# 01-PCIe.net
KiCad netlist of a schematic drawn in Altium Designer
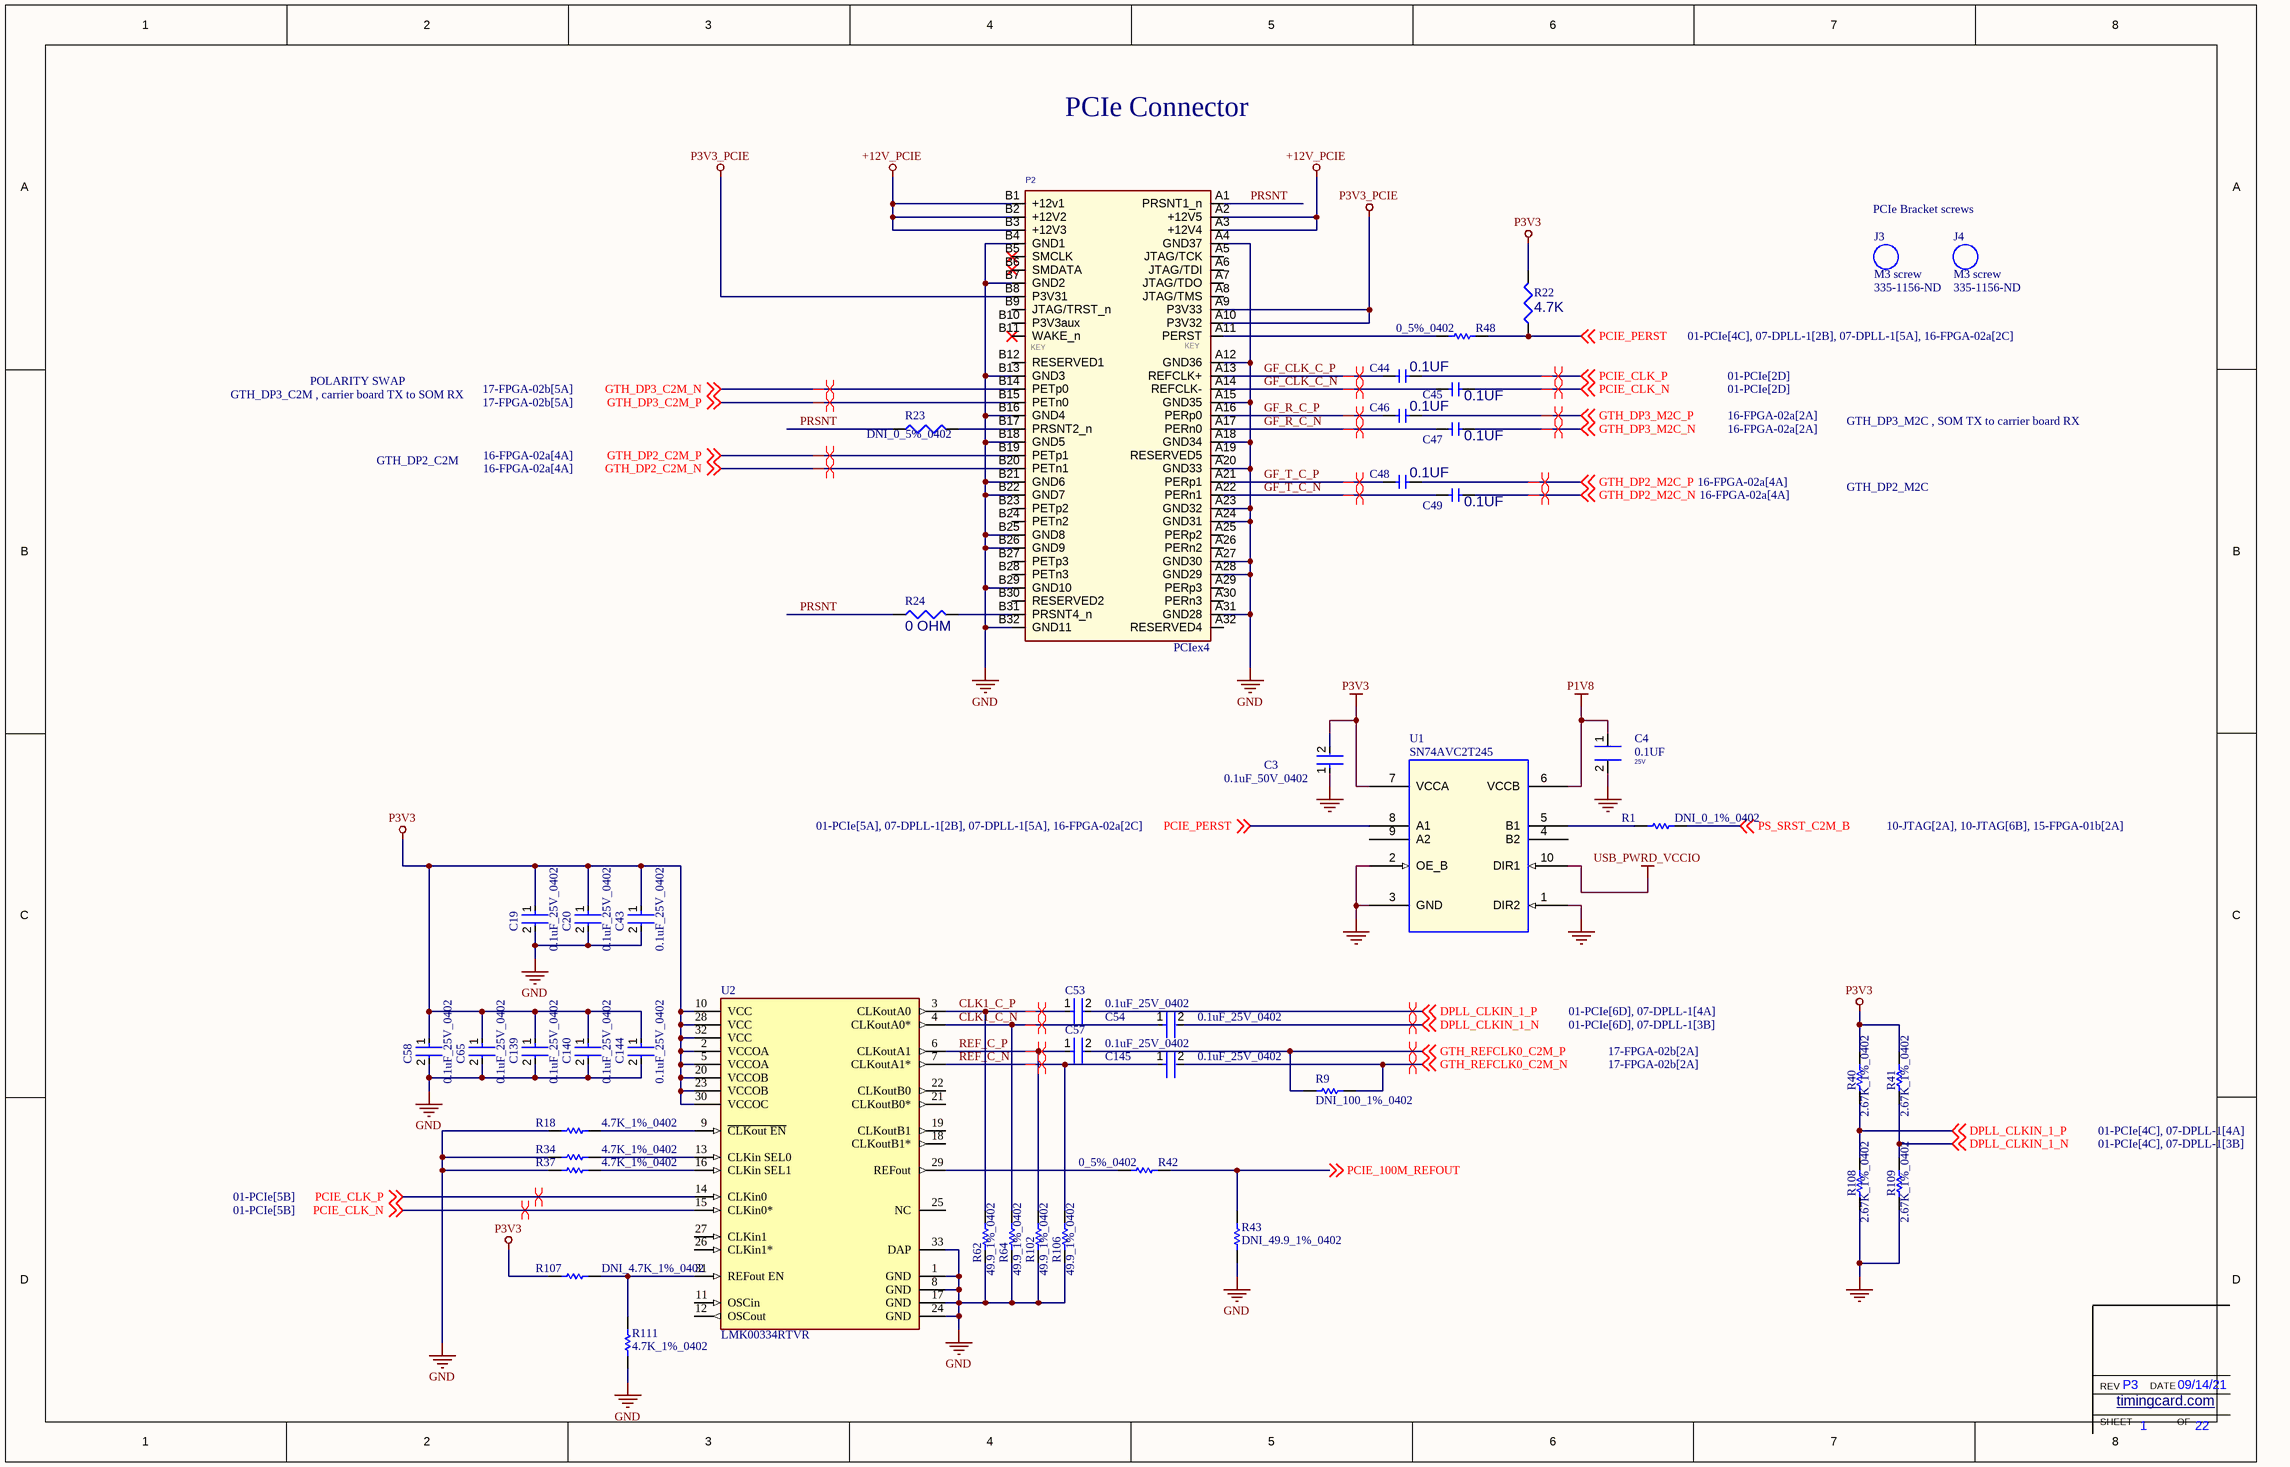
[diagram p0: 01-PCIe.SchDoc]

(export (version "E")
  (design (tool "Eeschema 10.0.6"))
  (components
    (comp (ref "C3")
      (value "0.1uF_50V_0402")
      (footprint "FP-C1005-050-0_05-IPC_C")
      (description "Multilayer Ceramic Capacitors 100nF ±10% 50V X7R SMD 0402")
      (fields (field (name "VOLTAGE") "50V") (field (name "TOLERANCE") "10%"))
      (libsource (lib "Altium Content Vault") (part "b4654b650e69147ec39a6b967a45e02"))
    )
    (comp (ref "C4")
      (value "0.1UF")
      (footprint "CAPC100X50X55")
      (description "Cap Cer 100nF 10% 25V X5R 0402")
      (fields
        (field (name "VOLTAGE") "25V")
        (field (name "MANUFACTURER") "TAIYO YUDEN")
        (field (name "AGILE PART NUMBER") "CAP-00068-01")
        (field (name "OWNER") "4001")
      )
      (libsource (lib "*") (part "CAP_NP"))
    )
    (comp (ref "C19")
      (value "0.1uF_25V_0402")
      (footprint "FP-0402-L_1_0_1-W_0_5_0_1-IPC_C")
      (description "General Purpose Ceramic Capacitor, 0402, 100nF, 10%, X7R, 15%, 25V")
      (fields (field (name "VOLTAGE") "25V") (field (name "TOLERANCE") "10%"))
      (libsource (lib "Altium Content Vault") (part "b4654b650e69147ec39a6b967a45e02"))
    )
    (comp (ref "C20")
      (value "0.1uF_25V_0402")
      (footprint "FP-0402-L_1_0_1-W_0_5_0_1-IPC_C")
      (description "General Purpose Ceramic Capacitor, 0402, 100nF, 10%, X7R, 15%, 25V")
      (fields (field (name "VOLTAGE") "25V") (field (name "TOLERANCE") "10%"))
      (libsource (lib "Altium Content Vault") (part "b4654b650e69147ec39a6b967a45e02"))
    )
    (comp (ref "C43")
      (value "0.1uF_25V_0402")
      (footprint "FP-0402-L_1_0_1-W_0_5_0_1-IPC_C")
      (description "General Purpose Ceramic Capacitor, 0402, 100nF, 10%, X7R, 15%, 25V")
      (fields (field (name "VOLTAGE") "25V") (field (name "TOLERANCE") "10%"))
      (libsource (lib "Altium Content Vault") (part "b4654b650e69147ec39a6b967a45e02"))
    )
    (comp (ref "C44")
      (value "0.1UF")
      (footprint "CAPC1005X06N")
      (description "CAP, CER, 0.1UF, 50V, 10%, X7R, AEC-Q200, 0402")
      (fields
        (field (name "MFG PART NUM") "CGA2B3X7R1H104K050BB")
        (field (name "VALENTIUM PART NUM") "<VALENTIUM>")
      )
      (libsource (lib "Capacitors") (part "CAP_0402_0.1UF_50V"))
    )
    (comp (ref "C45")
      (value "0.1UF")
      (footprint "CAPC1005X06N")
      (description "CAP, CER, 0.1UF, 50V, 10%, X7R, AEC-Q200, 0402")
      (fields
        (field (name "MFG PART NUM") "CGA2B3X7R1H104K050BB")
        (field (name "VALENTIUM PART NUM") "<VALENTIUM>")
      )
      (libsource (lib "Capacitors") (part "CAP_0402_0.1UF_50V"))
    )
    (comp (ref "C46")
      (value "0.1UF")
      (footprint "CAPC1005X06N")
      (description "CAP, CER, 0.1UF, 50V, 10%, X7R, AEC-Q200, 0402")
      (fields
        (field (name "MFG PART NUM") "CGA2B3X7R1H104K050BB")
        (field (name "VALENTIUM PART NUM") "<VALENTIUM>")
      )
      (libsource (lib "Capacitors") (part "CAP_0402_0.1UF_50V"))
    )
    (comp (ref "C47")
      (value "0.1UF")
      (footprint "CAPC1005X06N")
      (description "CAP, CER, 0.1UF, 50V, 10%, X7R, AEC-Q200, 0402")
      (fields
        (field (name "MFG PART NUM") "CGA2B3X7R1H104K050BB")
        (field (name "VALENTIUM PART NUM") "<VALENTIUM>")
      )
      (libsource (lib "Capacitors") (part "CAP_0402_0.1UF_50V"))
    )
    (comp (ref "C48")
      (value "0.1UF")
      (footprint "CAPC1005X06N")
      (description "CAP, CER, 0.1UF, 50V, 10%, X7R, AEC-Q200, 0402")
      (fields
        (field (name "MFG PART NUM") "CGA2B3X7R1H104K050BB")
        (field (name "VALENTIUM PART NUM") "<VALENTIUM>")
      )
      (libsource (lib "Capacitors") (part "CAP_0402_0.1UF_50V"))
    )
    (comp (ref "C49")
      (value "0.1UF")
      (footprint "CAPC1005X06N")
      (description "CAP, CER, 0.1UF, 50V, 10%, X7R, AEC-Q200, 0402")
      (fields
        (field (name "MFG PART NUM") "CGA2B3X7R1H104K050BB")
        (field (name "VALENTIUM PART NUM") "<VALENTIUM>")
      )
      (libsource (lib "Capacitors") (part "CAP_0402_0.1UF_50V"))
    )
    (comp (ref "C53")
      (value "0.1uF_25V_0402")
      (footprint "FP-0402-L_1_0_1-W_0_5_0_1-IPC_C")
      (description "General Purpose Ceramic Capacitor, 0402, 100nF, 10%, X7R, 15%, 25V")
      (fields (field (name "VOLTAGE") "25V") (field (name "TOLERANCE") "10%"))
      (libsource (lib "Altium Content Vault") (part "b4654b650e69147ec39a6b967a45e02"))
    )
    (comp (ref "C54")
      (value "0.1uF_25V_0402")
      (footprint "FP-0402-L_1_0_1-W_0_5_0_1-IPC_C")
      (description "General Purpose Ceramic Capacitor, 0402, 100nF, 10%, X7R, 15%, 25V")
      (fields (field (name "VOLTAGE") "25V") (field (name "TOLERANCE") "10%"))
      (libsource (lib "Altium Content Vault") (part "b4654b650e69147ec39a6b967a45e02"))
    )
    (comp (ref "C57")
      (value "0.1uF_25V_0402")
      (footprint "FP-0402-L_1_0_1-W_0_5_0_1-IPC_C")
      (description "General Purpose Ceramic Capacitor, 0402, 100nF, 10%, X7R, 15%, 25V")
      (fields (field (name "VOLTAGE") "25V") (field (name "TOLERANCE") "10%"))
      (libsource (lib "Altium Content Vault") (part "b4654b650e69147ec39a6b967a45e02"))
    )
    (comp (ref "C58")
      (value "0.1uF_25V_0402")
      (footprint "FP-0402-L_1_0_1-W_0_5_0_1-IPC_C")
      (description "General Purpose Ceramic Capacitor, 0402, 100nF, 10%, X7R, 15%, 25V")
      (fields (field (name "VOLTAGE") "25V") (field (name "TOLERANCE") "10%"))
      (libsource (lib "Altium Content Vault") (part "b4654b650e69147ec39a6b967a45e02"))
    )
    (comp (ref "C65")
      (value "0.1uF_25V_0402")
      (footprint "FP-0402-L_1_0_1-W_0_5_0_1-IPC_C")
      (description "General Purpose Ceramic Capacitor, 0402, 100nF, 10%, X7R, 15%, 25V")
      (fields (field (name "VOLTAGE") "25V") (field (name "TOLERANCE") "10%"))
      (libsource (lib "Altium Content Vault") (part "b4654b650e69147ec39a6b967a45e02"))
    )
    (comp (ref "C139")
      (value "0.1uF_25V_0402")
      (footprint "FP-0402-L_1_0_1-W_0_5_0_1-IPC_C")
      (description "General Purpose Ceramic Capacitor, 0402, 100nF, 10%, X7R, 15%, 25V")
      (fields (field (name "VOLTAGE") "25V") (field (name "TOLERANCE") "10%"))
      (libsource (lib "Altium Content Vault") (part "b4654b650e69147ec39a6b967a45e02"))
    )
    (comp (ref "C140")
      (value "0.1uF_25V_0402")
      (footprint "FP-0402-L_1_0_1-W_0_5_0_1-IPC_C")
      (description "General Purpose Ceramic Capacitor, 0402, 100nF, 10%, X7R, 15%, 25V")
      (fields (field (name "VOLTAGE") "25V") (field (name "TOLERANCE") "10%"))
      (libsource (lib "Altium Content Vault") (part "b4654b650e69147ec39a6b967a45e02"))
    )
    (comp (ref "C144")
      (value "0.1uF_25V_0402")
      (footprint "FP-0402-L_1_0_1-W_0_5_0_1-IPC_C")
      (description "General Purpose Ceramic Capacitor, 0402, 100nF, 10%, X7R, 15%, 25V")
      (fields (field (name "VOLTAGE") "25V") (field (name "TOLERANCE") "10%"))
      (libsource (lib "Altium Content Vault") (part "b4654b650e69147ec39a6b967a45e02"))
    )
    (comp (ref "C145")
      (value "0.1uF_25V_0402")
      (footprint "FP-0402-L_1_0_1-W_0_5_0_1-IPC_C")
      (description "General Purpose Ceramic Capacitor, 0402, 100nF, 10%, X7R, 15%, 25V")
      (fields (field (name "VOLTAGE") "25V") (field (name "TOLERANCE") "10%"))
      (libsource (lib "Altium Content Vault") (part "b4654b650e69147ec39a6b967a45e02"))
    )
    (comp (ref "J3")
      (value "M3 screw")
      (fields (field (name "SUPPLIER PART NUMBER 1") "335-1156-ND"))
      (libsource (lib "FPGA_CONN") (part "M3 screw"))
    )
    (comp (ref "J4")
      (value "M3 screw")
      (fields (field (name "SUPPLIER PART NUMBER 1") "335-1156-ND"))
      (libsource (lib "FPGA_CONN") (part "M3 screw"))
    )
    (comp (ref "P2")
      (value "PCIex4")
      (footprint "PCIE_4LANE_EDGE")
      (description "PCIE x4 Edge Connector,OrCAD Symbol,NC")
      (fields (field (name "PART NUMBER") "451") (field (name "MANUFACTURER") "NA"))
      (libsource (lib "Connectors") (part "PCIex4"))
    )
    (comp (ref "R1")
      (value "DNI_0_1%_0402")
      (footprint "RESC1005X40X25LL05T05")
      (description "Chip Resistor, 0 Ohm, 0.1 W, -55 to 155 degC, 0402 (1005 Metric), RoHS, Tape and Reel")
      (fields (field (name "MANUFACTURER") "Panasonic") (field (name "TOLERANCE") "5%"))
      (libsource (lib "Altium Content Vault") (part "RES-2"))
    )
    (comp (ref "R9")
      (value "DNI_100_1%_0402")
      (footprint "RESC1005X40X25ML05T10")
      (fields (field (name "PART NUMBER") "ERJ-U02F1000X") (field (name "MANUFACTURER") "Panasonic"))
      (libsource (lib "Altium Content Vault") (part "RES"))
    )
    (comp (ref "R18")
      (value "4.7K_1%_0402")
      (footprint "RESC1005X40X25NL10T10")
      (fields (field (name "MANUFACTURER") "Bourns") (field (name "PART NUMBER") "CR0402-FX-4701GLF"))
      (libsource (lib "Altium Content Vault") (part "RES"))
    )
    (comp (ref "R22")
      (value "4.7K")
      (footprint "RESC1608X50N")
      (description "RES, 4.7K, 1%, 1/10W, TF, 0603")
      (fields (field (name "MFG PART NUM") "ERJ-3EKF4701V") (field (name "VELENTIUM PART NUM") "<VELENTIUM>"))
      (libsource (lib "Resistors") (part "RES_0603_4.7K"))
    )
    (comp (ref "R23")
      (value "DNI_0_5%_0402")
      (footprint "RESC1005X04N")
      (description "RES, 0. OHM, 1%, 1/16W, TF, AEC-Q200, 0402")
      (fields (field (name "MFG PART NUM") "ERJ-2GE0R00X") (field (name "VELENTIUM PART NUM") "<VELENTIUM>"))
      (libsource (lib "Resistors") (part "RES_0402_0"))
    )
    (comp (ref "R24")
      (value "0 OHM")
      (footprint "RESC1005X04N")
      (description "RES, 0. OHM, 1%, 1/16W, TF, AEC-Q200, 0402")
      (fields (field (name "MFG PART NUM") "ERJ-2GE0R00X") (field (name "VELENTIUM PART NUM") "<VELENTIUM>"))
      (libsource (lib "Resistors") (part "RES_0402_0"))
    )
    (comp (ref "R34")
      (value "4.7K_1%_0402")
      (footprint "RESC1005X40X25NL10T10")
      (fields (field (name "MANUFACTURER") "Bourns") (field (name "PART NUMBER") "CR0402-FX-4701GLF"))
      (libsource (lib "Altium Content Vault") (part "RES"))
    )
    (comp (ref "R37")
      (value "4.7K_1%_0402")
      (footprint "RESC1005X40X25NL10T10")
      (fields (field (name "MANUFACTURER") "Bourns") (field (name "PART NUMBER") "CR0402-FX-4701GLF"))
      (libsource (lib "Altium Content Vault") (part "RES"))
    )
    (comp (ref "R40")
      (value "2.67K_1%_0402")
      (footprint "RESC1005X40X25NL05T10")
      (fields (field (name "MANUFACTURER") "Yageo") (field (name "PART NUMBER") "RC0402FR-072K67L"))
      (libsource (lib "Altium Content Vault") (part "RES"))
    )
    (comp (ref "R41")
      (value "2.67K_1%_0402")
      (footprint "RESC1005X40X25NL05T10")
      (fields (field (name "MANUFACTURER") "Yageo") (field (name "PART NUMBER") "RC0402FR-072K67L"))
      (libsource (lib "Altium Content Vault") (part "RES"))
    )
    (comp (ref "R42")
      (value "0_5%_0402")
      (footprint "RESC1005X40X25LL10T10")
      (fields (field (name "MANUFACTURER") "KOA Speer") (field (name "PART NUMBER") "RK73Z1ETTP"))
      (libsource (lib "Altium Content Vault") (part "RES"))
    )
    (comp (ref "R43")
      (value "DNI_49.9_1%_0402")
      (footprint "RESC1005X40X25NL10T10")
      (fields (field (name "PART NUMBER") "RK73H1ETTP49R9F") (field (name "MANUFACTURER") "KOA Speer"))
      (libsource (lib "Altium Content Vault") (part "RES"))
    )
    (comp (ref "R48")
      (value "0_5%_0402")
      (footprint "RESC1005X40X25LL10T10")
      (fields (field (name "MANUFACTURER") "KOA Speer") (field (name "PART NUMBER") "RK73Z1ETTP"))
      (libsource (lib "Altium Content Vault") (part "RES"))
    )
    (comp (ref "R62")
      (value "49.9_1%_0402")
      (footprint "RESC1005X40X25NL10T10")
      (fields (field (name "PART NUMBER") "RK73H1ETTP49R9F") (field (name "MANUFACTURER") "KOA Speer"))
      (libsource (lib "Altium Content Vault") (part "RES"))
    )
    (comp (ref "R64")
      (value "49.9_1%_0402")
      (footprint "RESC1005X40X25NL10T10")
      (fields (field (name "PART NUMBER") "RK73H1ETTP49R9F") (field (name "MANUFACTURER") "KOA Speer"))
      (libsource (lib "Altium Content Vault") (part "RES"))
    )
    (comp (ref "R102")
      (value "49.9_1%_0402")
      (footprint "RESC1005X40X25NL10T10")
      (fields (field (name "PART NUMBER") "RK73H1ETTP49R9F") (field (name "MANUFACTURER") "KOA Speer"))
      (libsource (lib "Altium Content Vault") (part "RES"))
    )
    (comp (ref "R106")
      (value "49.9_1%_0402")
      (footprint "RESC1005X40X25NL10T10")
      (fields (field (name "PART NUMBER") "RK73H1ETTP49R9F") (field (name "MANUFACTURER") "KOA Speer"))
      (libsource (lib "Altium Content Vault") (part "RES"))
    )
    (comp (ref "R107")
      (value "DNI_4.7K_1%_0402")
      (footprint "RESC1005X40X25NL10T10")
      (fields (field (name "MANUFACTURER") "Bourns") (field (name "PART NUMBER") "CR0402-FX-4701GLF"))
      (libsource (lib "Altium Content Vault") (part "RES"))
    )
    (comp (ref "R108")
      (value "2.67K_1%_0402")
      (footprint "RESC1005X40X25NL05T10")
      (fields (field (name "MANUFACTURER") "Yageo") (field (name "PART NUMBER") "RC0402FR-072K67L"))
      (libsource (lib "Altium Content Vault") (part "RES"))
    )
    (comp (ref "R109")
      (value "2.67K_1%_0402")
      (footprint "RESC1005X40X25NL05T10")
      (fields (field (name "MANUFACTURER") "Yageo") (field (name "PART NUMBER") "RC0402FR-072K67L"))
      (libsource (lib "Altium Content Vault") (part "RES"))
    )
    (comp (ref "R111")
      (value "4.7K_1%_0402")
      (footprint "RESC1005X40X25NL10T10")
      (fields (field (name "MANUFACTURER") "Bourns") (field (name "PART NUMBER") "CR0402-FX-4701GLF"))
      (libsource (lib "Altium Content Vault") (part "RES"))
    )
    (comp (ref "U1")
      (value "SN74AVC2T245")
      (footprint "QFN40P140X180X55-10")
      (description "IC Lvl Trans 2-Bit Bidir 500Mbps 1.2-3.6V 50mA UQFN-10")
      (fields
        (field (name "MANUFACTURER") "TEXAS INSTRUMENTS")
        (field (name "AGILE PART NUMBER") "ICS-00048-01")
      )
      (libsource (lib "*") (part "SN74AVC2T245"))
    )
    (comp (ref "U2")
      (value "LMK00334RTVR")
      (footprint "FP-RTV0032A-MFG")
      (description "IC CLK BUF 400MHZ 1CIRC 32WQFN")
      (libsource (lib "Altium Content Vault") (part "b0788d09999557299357136416a342e"))
    )
  )
  (nets
    (net (code "1") (name "+12V_PCIE") (class "Default")
      (node (ref "P2") (pin "A2") (pinfunction "+12V5_A2") (pintype "passive"))
      (node (ref "P2") (pin "A3") (pinfunction "+12V4_A3") (pintype "passive"))
      (node (ref "P2") (pin "B1") (pinfunction "+12v1_B1") (pintype "power_in"))
      (node (ref "P2") (pin "B2") (pinfunction "+12V2_B2") (pintype "power_in"))
      (node (ref "P2") (pin "B3") (pinfunction "+12V3_B3") (pintype "power_in"))
    )
    (net (code "2") (name "/CLK1_C_N") (class "Default")
      (node (ref "C54") (pin "1") (pinfunction "1_1") (pintype "passive"))
      (node (ref "R64") (pin "2") (pinfunction "2_2") (pintype "passive"))
      (node (ref "U2") (pin "4") (pinfunction "CLKoutA0*_4") (pintype "output"))
    )
    (net (code "3") (name "/CLK1_C_P") (class "Default")
      (node (ref "C53") (pin "1") (pinfunction "1_1") (pintype "passive"))
      (node (ref "R62") (pin "2") (pinfunction "2_2") (pintype "passive"))
      (node (ref "U2") (pin "3") (pinfunction "CLKoutA0_3") (pintype "output"))
    )
    (net (code "4") (name "/GF_CLK_C_N") (class "Default")
      (node (ref "C45") (pin "1") (pinfunction "1_1") (pintype "passive"))
      (node (ref "P2") (pin "A14") (pinfunction "REFCLK-_A14") (pintype "passive"))
    )
    (net (code "5") (name "/GF_CLK_C_P") (class "Default")
      (node (ref "C44") (pin "1") (pinfunction "1_1") (pintype "passive"))
      (node (ref "P2") (pin "A13") (pinfunction "REFCLK+_A13") (pintype "passive"))
    )
    (net (code "6") (name "/GF_R_C_N") (class "Default")
      (node (ref "C47") (pin "1") (pinfunction "1_1") (pintype "passive"))
      (node (ref "P2") (pin "A17") (pinfunction "PERn0_A17") (pintype "passive"))
    )
    (net (code "7") (name "/GF_R_C_P") (class "Default")
      (node (ref "C46") (pin "1") (pinfunction "1_1") (pintype "passive"))
      (node (ref "P2") (pin "A16") (pinfunction "PERp0_A16") (pintype "passive"))
    )
    (net (code "8") (name "/GF_T_C_N") (class "Default")
      (node (ref "C49") (pin "1") (pinfunction "1_1") (pintype "passive"))
      (node (ref "P2") (pin "A22") (pinfunction "PERn1_A22") (pintype "passive"))
    )
    (net (code "9") (name "/GF_T_C_P") (class "Default")
      (node (ref "C48") (pin "1") (pinfunction "1_1") (pintype "passive"))
      (node (ref "P2") (pin "A21") (pinfunction "PERp1_A21") (pintype "passive"))
    )
    (net (code "10") (name "/PRSNT") (class "Default")
      (node (ref "P2") (pin "A1") (pinfunction "PRSNT1_n_A1") (pintype "passive"))
      (node (ref "R23") (pin "1") (pinfunction "1_1") (pintype "passive"))
      (node (ref "R24") (pin "1") (pinfunction "1_1") (pintype "passive"))
    )
    (net (code "11") (name "/REF_C_N") (class "Default")
      (node (ref "C145") (pin "1") (pinfunction "1_1") (pintype "passive"))
      (node (ref "R106") (pin "2") (pinfunction "2_2") (pintype "passive"))
      (node (ref "U2") (pin "7") (pinfunction "CLKoutA1*_7") (pintype "output"))
    )
    (net (code "12") (name "/REF_C_P") (class "Default")
      (node (ref "C57") (pin "1") (pinfunction "1_1") (pintype "passive"))
      (node (ref "R102") (pin "2") (pinfunction "2_2") (pintype "passive"))
      (node (ref "U2") (pin "6") (pinfunction "CLKoutA1_6") (pintype "output"))
    )
    (net (code "13") (name "DPLL_CLKIN_1_N") (class "Default")
      (node (ref "C54") (pin "2") (pinfunction "2_2") (pintype "passive"))
      (node (ref "R109") (pin "2") (pinfunction "2_2") (pintype "passive"))
      (node (ref "R41") (pin "1") (pinfunction "1_1") (pintype "passive"))
    )
    (net (code "14") (name "DPLL_CLKIN_1_P") (class "Default")
      (node (ref "C53") (pin "2") (pinfunction "2_2") (pintype "passive"))
      (node (ref "R108") (pin "2") (pinfunction "2_2") (pintype "passive"))
      (node (ref "R40") (pin "1") (pinfunction "1_1") (pintype "passive"))
    )
    (net (code "15") (name "GND") (class "Default")
      (node (ref "C139") (pin "2") (pinfunction "2_2") (pintype "passive"))
      (node (ref "C140") (pin "2") (pinfunction "2_2") (pintype "passive"))
      (node (ref "C144") (pin "2") (pinfunction "2_2") (pintype "passive"))
      (node (ref "C19") (pin "2") (pinfunction "2_2") (pintype "passive"))
      (node (ref "C20") (pin "2") (pinfunction "2_2") (pintype "passive"))
      (node (ref "C3") (pin "1") (pinfunction "1_1") (pintype "passive"))
      (node (ref "C4") (pin "2") (pinfunction "2_2") (pintype "passive"))
      (node (ref "C43") (pin "2") (pinfunction "2_2") (pintype "passive"))
      (node (ref "C58") (pin "2") (pinfunction "2_2") (pintype "passive"))
      (node (ref "C65") (pin "2") (pinfunction "2_2") (pintype "passive"))
      (node (ref "P2") (pin "A12") (pinfunction "GND36_A12") (pintype "power_in"))
      (node (ref "P2") (pin "A15") (pinfunction "GND35_A15") (pintype "power_in"))
      (node (ref "P2") (pin "A18") (pinfunction "GND34_A18") (pintype "power_in"))
      (node (ref "P2") (pin "A20") (pinfunction "GND33_A20") (pintype "power_in"))
      (node (ref "P2") (pin "A23") (pinfunction "GND32_A23") (pintype "power_in"))
      (node (ref "P2") (pin "A24") (pinfunction "GND31_A24") (pintype "power_in"))
      (node (ref "P2") (pin "A27") (pinfunction "GND30_A27") (pintype "power_in"))
      (node (ref "P2") (pin "A28") (pinfunction "GND29_A28") (pintype "power_in"))
      (node (ref "P2") (pin "A31") (pinfunction "GND28_A31") (pintype "power_in"))
      (node (ref "P2") (pin "A4") (pinfunction "GND37_A4") (pintype "power_in"))
      (node (ref "P2") (pin "B13") (pinfunction "GND3_B13") (pintype "power_in"))
      (node (ref "P2") (pin "B16") (pinfunction "GND4_B16") (pintype "power_in"))
      (node (ref "P2") (pin "B18") (pinfunction "GND5_B18") (pintype "power_in"))
      (node (ref "P2") (pin "B21") (pinfunction "GND6_B21") (pintype "power_in"))
      (node (ref "P2") (pin "B22") (pinfunction "GND7_B22") (pintype "power_in"))
      (node (ref "P2") (pin "B25") (pinfunction "GND8_B25") (pintype "power_in"))
      (node (ref "P2") (pin "B26") (pinfunction "GND9_B26") (pintype "power_in"))
      (node (ref "P2") (pin "B29") (pinfunction "GND10_B29") (pintype "power_in"))
      (node (ref "P2") (pin "B32") (pinfunction "GND11_B32") (pintype "power_in"))
      (node (ref "P2") (pin "B4") (pinfunction "GND1_B4") (pintype "power_in"))
      (node (ref "P2") (pin "B7") (pinfunction "GND2_B7") (pintype "power_in"))
      (node (ref "R102") (pin "1") (pinfunction "1_1") (pintype "passive"))
      (node (ref "R106") (pin "1") (pinfunction "1_1") (pintype "passive"))
      (node (ref "R108") (pin "1") (pinfunction "1_1") (pintype "passive"))
      (node (ref "R109") (pin "1") (pinfunction "1_1") (pintype "passive"))
      (node (ref "R111") (pin "2") (pinfunction "2_2") (pintype "passive"))
      (node (ref "R18") (pin "2") (pinfunction "2_2") (pintype "passive"))
      (node (ref "R34") (pin "2") (pinfunction "2_2") (pintype "passive"))
      (node (ref "R37") (pin "2") (pinfunction "2_2") (pintype "passive"))
      (node (ref "R43") (pin "2") (pinfunction "2_2") (pintype "passive"))
      (node (ref "R62") (pin "1") (pinfunction "1_1") (pintype "passive"))
      (node (ref "R64") (pin "1") (pinfunction "1_1") (pintype "passive"))
      (node (ref "U1") (pin "1") (pinfunction "DIR2_1") (pintype "input"))
      (node (ref "U1") (pin "2") (pinfunction "OE_B_2") (pintype "input"))
      (node (ref "U1") (pin "3") (pinfunction "GND_3") (pintype "power_in"))
      (node (ref "U2") (pin "1") (pinfunction "GND_1") (pintype "power_in"))
      (node (ref "U2") (pin "17") (pinfunction "GND_17") (pintype "power_in"))
      (node (ref "U2") (pin "24") (pinfunction "GND_24") (pintype "power_in"))
      (node (ref "U2") (pin "33") (pinfunction "DAP_33") (pintype "power_in"))
      (node (ref "U2") (pin "8") (pinfunction "GND_8") (pintype "power_in"))
    )
    (net (code "16") (name "GTH_DP2_C2M_N") (class "Default")
      (node (ref "P2") (pin "B20") (pinfunction "PETn1_B20") (pintype "passive"))
    )
    (net (code "17") (name "GTH_DP2_C2M_P") (class "Default")
      (node (ref "P2") (pin "B19") (pinfunction "PETp1_B19") (pintype "passive"))
    )
    (net (code "18") (name "GTH_DP2_M2C_N") (class "Default")
      (node (ref "C49") (pin "2") (pinfunction "2_2") (pintype "passive"))
    )
    (net (code "19") (name "GTH_DP2_M2C_P") (class "Default")
      (node (ref "C48") (pin "2") (pinfunction "2_2") (pintype "passive"))
    )
    (net (code "20") (name "GTH_DP3_C2M_N") (class "Default")
      (node (ref "P2") (pin "B14") (pinfunction "PETp0_B14") (pintype "passive"))
    )
    (net (code "21") (name "GTH_DP3_C2M_P") (class "Default")
      (node (ref "P2") (pin "B15") (pinfunction "PETn0_B15") (pintype "passive"))
    )
    (net (code "22") (name "GTH_DP3_M2C_N") (class "Default")
      (node (ref "C47") (pin "2") (pinfunction "2_2") (pintype "passive"))
    )
    (net (code "23") (name "GTH_DP3_M2C_P") (class "Default")
      (node (ref "C46") (pin "2") (pinfunction "2_2") (pintype "passive"))
    )
    (net (code "24") (name "GTH_REFCLK0_C2M_N") (class "Default")
      (node (ref "C145") (pin "2") (pinfunction "2_2") (pintype "passive"))
      (node (ref "R9") (pin "2") (pinfunction "2_2") (pintype "passive"))
    )
    (net (code "25") (name "GTH_REFCLK0_C2M_P") (class "Default")
      (node (ref "C57") (pin "2") (pinfunction "2_2") (pintype "passive"))
      (node (ref "R9") (pin "1") (pinfunction "1_1") (pintype "passive"))
    )
    (net (code "26") (name "Net-(P2-PERST)") (class "Default")
      (node (ref "P2") (pin "A11") (pinfunction "PERST_A11") (pintype "passive"))
      (node (ref "R48") (pin "1") (pinfunction "1_1") (pintype "passive"))
    )
    (net (code "27") (name "Net-(P2-PRSNT2_n)") (class "Default")
      (node (ref "P2") (pin "B17") (pinfunction "PRSNT2_n_B17") (pintype "passive"))
      (node (ref "R23") (pin "2") (pinfunction "2_2") (pintype "passive"))
    )
    (net (code "28") (name "Net-(P2-PRSNT4_n)") (class "Default")
      (node (ref "P2") (pin "B31") (pinfunction "PRSNT4_n_B31") (pintype "passive"))
      (node (ref "R24") (pin "2") (pinfunction "2_2") (pintype "passive"))
    )
    (net (code "29") (name "Net-(U1-B1)") (class "Default")
      (node (ref "R1") (pin "1") (pinfunction "1_1") (pintype "passive"))
      (node (ref "U1") (pin "5") (pinfunction "B1_5") (pintype "passive"))
    )
    (net (code "30") (name "Net-(U2-CLKin_SEL0)") (class "Default")
      (node (ref "R34") (pin "1") (pinfunction "1_1") (pintype "passive"))
      (node (ref "U2") (pin "13") (pinfunction "CLKin_SEL0_13") (pintype "input"))
    )
    (net (code "31") (name "Net-(U2-CLKin_SEL1)") (class "Default")
      (node (ref "R37") (pin "1") (pinfunction "1_1") (pintype "passive"))
      (node (ref "U2") (pin "16") (pinfunction "CLKin_SEL1_16") (pintype "input"))
    )
    (net (code "32") (name "Net-(U2-REFout)") (class "Default")
      (node (ref "R42") (pin "1") (pinfunction "1_1") (pintype "passive"))
      (node (ref "U2") (pin "29") (pinfunction "REFout_29") (pintype "output"))
    )
    (net (code "33") (name "Net-(U2-REFout_EN)") (class "Default")
      (node (ref "R107") (pin "1") (pinfunction "1_1") (pintype "passive"))
      (node (ref "R111") (pin "1") (pinfunction "1_1") (pintype "passive"))
      (node (ref "U2") (pin "31") (pinfunction "REFout_EN_31") (pintype "input"))
    )
    (net (code "34") (name "Net-(U2-~{CLKout_EN})") (class "Default")
      (node (ref "R18") (pin "1") (pinfunction "1_1") (pintype "passive"))
      (node (ref "U2") (pin "9") (pinfunction "~{CLKout_EN}_9") (pintype "input"))
    )
    (net (code "35") (name "P1V8") (class "Default")
      (node (ref "C4") (pin "1") (pinfunction "1_1") (pintype "passive"))
      (node (ref "U1") (pin "6") (pinfunction "VCCB_6") (pintype "power_in"))
    )
    (net (code "36") (name "P3V3") (class "Default")
      (node (ref "C139") (pin "1") (pinfunction "1_1") (pintype "passive"))
      (node (ref "C140") (pin "1") (pinfunction "1_1") (pintype "passive"))
      (node (ref "C144") (pin "1") (pinfunction "1_1") (pintype "passive"))
      (node (ref "C19") (pin "1") (pinfunction "1_1") (pintype "passive"))
      (node (ref "C20") (pin "1") (pinfunction "1_1") (pintype "passive"))
      (node (ref "C3") (pin "2") (pinfunction "2_2") (pintype "passive"))
      (node (ref "C43") (pin "1") (pinfunction "1_1") (pintype "passive"))
      (node (ref "C58") (pin "1") (pinfunction "1_1") (pintype "passive"))
      (node (ref "C65") (pin "1") (pinfunction "1_1") (pintype "passive"))
      (node (ref "R107") (pin "2") (pinfunction "2_2") (pintype "passive"))
      (node (ref "R22") (pin "2") (pinfunction "2_2") (pintype "passive"))
      (node (ref "R40") (pin "2") (pinfunction "2_2") (pintype "passive"))
      (node (ref "R41") (pin "2") (pinfunction "2_2") (pintype "passive"))
      (node (ref "U1") (pin "7") (pinfunction "VCCA_7") (pintype "power_in"))
      (node (ref "U2") (pin "10") (pinfunction "VCC_10") (pintype "power_in"))
      (node (ref "U2") (pin "2") (pinfunction "VCCOA_2") (pintype "power_in"))
      (node (ref "U2") (pin "20") (pinfunction "VCCOB_20") (pintype "power_in"))
      (node (ref "U2") (pin "23") (pinfunction "VCCOB_23") (pintype "power_in"))
      (node (ref "U2") (pin "28") (pinfunction "VCC_28") (pintype "power_in"))
      (node (ref "U2") (pin "30") (pinfunction "VCCOC_30") (pintype "power_in"))
      (node (ref "U2") (pin "32") (pinfunction "VCC_32") (pintype "power_in"))
      (node (ref "U2") (pin "5") (pinfunction "VCCOA_5") (pintype "power_in"))
    )
    (net (code "37") (name "P3V3_PCIE") (class "Default")
      (node (ref "P2") (pin "A10") (pinfunction "P3V32_A10") (pintype "passive"))
      (node (ref "P2") (pin "A9") (pinfunction "P3V33_A9") (pintype "passive"))
      (node (ref "P2") (pin "B8") (pinfunction "P3V31_B8") (pintype "power_in"))
    )
    (net (code "38") (name "PCIE_100M_REFOUT") (class "Default")
      (node (ref "R42") (pin "2") (pinfunction "2_2") (pintype "passive"))
      (node (ref "R43") (pin "1") (pinfunction "1_1") (pintype "passive"))
    )
    (net (code "39") (name "PCIE_CLK_N") (class "Default")
      (node (ref "C45") (pin "2") (pinfunction "2_2") (pintype "passive"))
      (node (ref "U2") (pin "15") (pinfunction "CLKin0*_15") (pintype "input"))
    )
    (net (code "40") (name "PCIE_CLK_P") (class "Default")
      (node (ref "C44") (pin "2") (pinfunction "2_2") (pintype "passive"))
      (node (ref "U2") (pin "14") (pinfunction "CLKin0_14") (pintype "input"))
    )
    (net (code "41") (name "PCIE_PERST") (class "Default")
      (node (ref "R22") (pin "1") (pinfunction "1_1") (pintype "passive"))
      (node (ref "R48") (pin "2") (pinfunction "2_2") (pintype "passive"))
      (node (ref "U1") (pin "8") (pinfunction "A1_8") (pintype "passive"))
    )
    (net (code "42") (name "PS_SRST_C2M_B") (class "Default")
      (node (ref "R1") (pin "2") (pinfunction "2_2") (pintype "passive"))
    )
    (net (code "43") (name "USB_PWRD_VCCIO") (class "Default")
      (node (ref "U1") (pin "10") (pinfunction "DIR1_10") (pintype "input"))
    )
    (net (code "44") (name "unconnected-(P2-JTAG{slash}TCK-PadA5)") (class "Default")
      (node (ref "P2") (pin "A5") (pinfunction "JTAG/TCK_A5") (pintype "passive"))
    )
    (net (code "45") (name "unconnected-(P2-JTAG{slash}TDI-PadA6)") (class "Default")
      (node (ref "P2") (pin "A6") (pinfunction "JTAG/TDI_A6") (pintype "passive"))
    )
    (net (code "46") (name "unconnected-(P2-JTAG{slash}TDO-PadA7)") (class "Default")
      (node (ref "P2") (pin "A7") (pinfunction "JTAG/TDO_A7") (pintype "passive"))
    )
    (net (code "47") (name "unconnected-(P2-JTAG{slash}TMS-PadA8)") (class "Default")
      (node (ref "P2") (pin "A8") (pinfunction "JTAG/TMS_A8") (pintype "passive"))
    )
    (net (code "48") (name "unconnected-(P2-JTAG{slash}TRST_n-PadB9)") (class "Default")
      (node (ref "P2") (pin "B9") (pinfunction "JTAG/TRST_n_B9") (pintype "passive"))
    )
    (net (code "49") (name "unconnected-(P2-P3V3aux-PadB10)") (class "Default")
      (node (ref "P2") (pin "B10") (pinfunction "P3V3aux_B10") (pintype "passive"))
    )
    (net (code "50") (name "unconnected-(P2-PERn2-PadA26)") (class "Default")
      (node (ref "P2") (pin "A26") (pinfunction "PERn2_A26") (pintype "passive"))
    )
    (net (code "51") (name "unconnected-(P2-PERn3-PadA30)") (class "Default")
      (node (ref "P2") (pin "A30") (pinfunction "PERn3_A30") (pintype "passive"))
    )
    (net (code "52") (name "unconnected-(P2-PERp2-PadA25)") (class "Default")
      (node (ref "P2") (pin "A25") (pinfunction "PERp2_A25") (pintype "passive"))
    )
    (net (code "53") (name "unconnected-(P2-PERp3-PadA29)") (class "Default")
      (node (ref "P2") (pin "A29") (pinfunction "PERp3_A29") (pintype "passive"))
    )
    (net (code "54") (name "unconnected-(P2-PETn2-PadB24)") (class "Default")
      (node (ref "P2") (pin "B24") (pinfunction "PETn2_B24") (pintype "passive"))
    )
    (net (code "55") (name "unconnected-(P2-PETn3-PadB28)") (class "Default")
      (node (ref "P2") (pin "B28") (pinfunction "PETn3_B28") (pintype "passive"))
    )
    (net (code "56") (name "unconnected-(P2-PETp2-PadB23)") (class "Default")
      (node (ref "P2") (pin "B23") (pinfunction "PETp2_B23") (pintype "passive"))
    )
    (net (code "57") (name "unconnected-(P2-PETp3-PadB27)") (class "Default")
      (node (ref "P2") (pin "B27") (pinfunction "PETp3_B27") (pintype "passive"))
    )
    (net (code "58") (name "unconnected-(P2-RESERVED1-PadB12)") (class "Default")
      (node (ref "P2") (pin "B12") (pinfunction "RESERVED1_B12") (pintype "passive"))
    )
    (net (code "59") (name "unconnected-(P2-RESERVED2-PadB30)") (class "Default")
      (node (ref "P2") (pin "B30") (pinfunction "RESERVED2_B30") (pintype "passive"))
    )
    (net (code "60") (name "unconnected-(P2-RESERVED4-PadA32)") (class "Default")
      (node (ref "P2") (pin "A32") (pinfunction "RESERVED4_A32") (pintype "passive"))
    )
    (net (code "61") (name "unconnected-(P2-RESERVED5-PadA19)") (class "Default")
      (node (ref "P2") (pin "A19") (pinfunction "RESERVED5_A19") (pintype "passive"))
    )
    (net (code "62") (name "unconnected-(P2-SMCLK-PadB5)") (class "Default")
      (node (ref "P2") (pin "B5") (pinfunction "SMCLK_B5") (pintype "passive+no_connect"))
    )
    (net (code "63") (name "unconnected-(P2-SMDATA-PadB6)") (class "Default")
      (node (ref "P2") (pin "B6") (pinfunction "SMDATA_B6") (pintype "passive+no_connect"))
    )
    (net (code "64") (name "unconnected-(P2-WAKE_n-PadB11)") (class "Default")
      (node (ref "P2") (pin "B11") (pinfunction "WAKE_n_B11") (pintype "passive+no_connect"))
    )
    (net (code "65") (name "unconnected-(U1-A2-Pad9)") (class "Default")
      (node (ref "U1") (pin "9") (pinfunction "A2_9") (pintype "passive"))
    )
    (net (code "66") (name "unconnected-(U1-B2-Pad4)") (class "Default")
      (node (ref "U1") (pin "4") (pinfunction "B2_4") (pintype "passive"))
    )
    (net (code "67") (name "unconnected-(U2-CLKin1*-Pad26)") (class "Default")
      (node (ref "U2") (pin "26") (pinfunction "CLKin1*_26") (pintype "input"))
    )
    (net (code "68") (name "unconnected-(U2-CLKin1-Pad27)") (class "Default")
      (node (ref "U2") (pin "27") (pinfunction "CLKin1_27") (pintype "input"))
    )
    (net (code "69") (name "unconnected-(U2-CLKoutB0*-Pad21)") (class "Default")
      (node (ref "U2") (pin "21") (pinfunction "CLKoutB0*_21") (pintype "output"))
    )
    (net (code "70") (name "unconnected-(U2-CLKoutB0-Pad22)") (class "Default")
      (node (ref "U2") (pin "22") (pinfunction "CLKoutB0_22") (pintype "output"))
    )
    (net (code "71") (name "unconnected-(U2-CLKoutB1*-Pad18)") (class "Default")
      (node (ref "U2") (pin "18") (pinfunction "CLKoutB1*_18") (pintype "output"))
    )
    (net (code "72") (name "unconnected-(U2-CLKoutB1-Pad19)") (class "Default")
      (node (ref "U2") (pin "19") (pinfunction "CLKoutB1_19") (pintype "output"))
    )
    (net (code "73") (name "unconnected-(U2-NC-Pad25)") (class "Default")
      (node (ref "U2") (pin "25") (pinfunction "NC_25") (pintype "passive"))
    )
    (net (code "74") (name "unconnected-(U2-OSCin-Pad11)") (class "Default")
      (node (ref "U2") (pin "11") (pinfunction "OSCin_11") (pintype "input"))
    )
    (net (code "75") (name "unconnected-(U2-OSCout-Pad12)") (class "Default")
      (node (ref "U2") (pin "12") (pinfunction "OSCout_12") (pintype "output"))
    )
  )
)
